# SH3_-_RS-485.net
KiCad netlist of a schematic drawn in Altium Designer
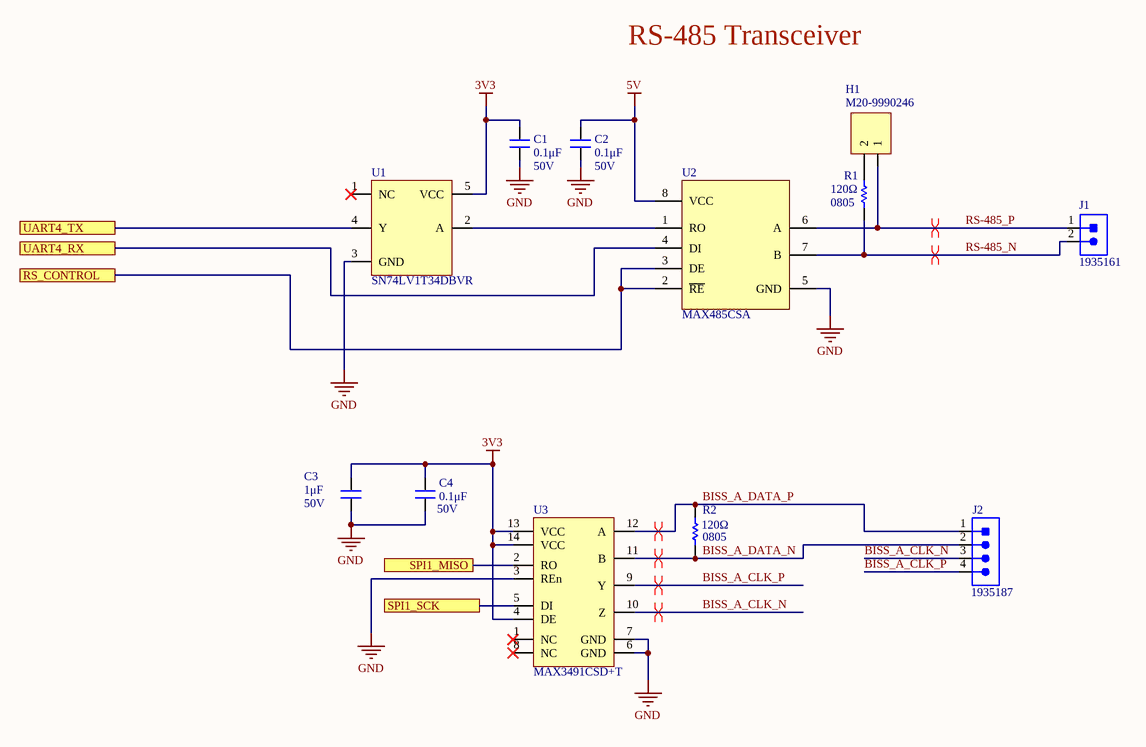
[diagram p0: SH3 - RS-485.SchDoc]

(export (version "E")
  (design (tool "Eeschema 10.0.6"))
  (components
    (comp (ref "C1")
      (value "0.1μF")
      (footprint "CAP2012")
      (description "CAP CER 0.1UF 50V X7R 0805")
      (fields
        (field (name "VOLTAGE RATING") "50V")
        (field (name "LCSC PART #") "C49678")
        (field (name "Comment") "CAP_0.1uF_50V_0805")
      )
      (libsource (lib "UWRT_Schematic_Library_2020") (part "CAP_0.1uF_50V_0805"))
    )
    (comp (ref "C2")
      (value "0.1μF")
      (footprint "CAP2012")
      (description "CAP CER 0.1UF 50V X7R 0805")
      (fields
        (field (name "VOLTAGE RATING") "50V")
        (field (name "LCSC PART #") "C49678")
        (field (name "Comment") "CAP_0.1uF_50V_0805")
      )
      (libsource (lib "UWRT_Schematic_Library_2020") (part "CAP_0.1uF_50V_0805"))
    )
    (comp (ref "C3")
      (value "1μF")
      (footprint "CAP2012")
      (description "CAP CER 1UF 50V X7R 0805")
      (fields
        (field (name "VOLTAGE RATING") "50V")
        (field (name "LCSC PART #") "C28323")
        (field (name "Comment") "CAP_1uF_50V_0805")
      )
      (libsource (lib "UWRT_Schematic_Library_2020") (part "CAP_1uF_50V_0805"))
    )
    (comp (ref "C4")
      (value "0.1μF")
      (footprint "CAP2012")
      (description "CAP CER 0.1UF 50V X7R 0805")
      (fields
        (field (name "VOLTAGE RATING") "50V")
        (field (name "LCSC PART #") "C49678")
        (field (name "Comment") "CAP_0.1uF_50V_0805")
      )
      (libsource (lib "UWRT_Schematic_Library_2020") (part "CAP_0.1uF_50V_0805"))
    )
    (comp (ref "H1")
      (value "JUMPER")
      (footprint "HDR1X2")
      (description "HEADER 2X1")
      (fields (field (name "MANUFACTURER PART NUMBER 1") "M20-9990246"))
      (libsource (lib "UWRT_Schematic_Library_2020") (part "JUMPER"))
    )
    (comp (ref "J1")
      (value "CON_2POS_SCREW_TERM")
      (footprint "1935161")
      (description "TERM BLK 2POS SIDE ENTRY 5MM")
      (fields (field (name "MANUFACTURER PART NUMBER 1") "1935161"))
      (libsource (lib "UWRT_Schematic_Library_2020") (part "CON_2POS_SCREW_TERM"))
    )
    (comp (ref "J2")
      (value "CON_4POS_SCREW_TERM")
      (footprint "1935187")
      (description "TERM BLK 4POS SIDE ENTRY 5MM")
      (fields (field (name "MANUFACTURER PART NUMBER 1") "1935187"))
      (libsource (lib "UWRT_Schematic_Library_2020") (part "CON_4POS_SCREW_TERM"))
    )
    (comp (ref "R1")
      (value "120Ω")
      (footprint "RESC0805")
      (description "RES 120 OHM 1% 1/8W 0805")
      (fields
        (field (name "LCSC PART #") "C17437")
        (field (name "PACKAGE/FOOTPRINT") "0805")
        (field (name "Comment") "RES_120Ω_0805_1%")
      )
      (libsource (lib "UWRT_Schematic_Library_2020") (part "RES_120Ω_0805_1%"))
    )
    (comp (ref "R2")
      (value "120Ω")
      (footprint "RESC0805")
      (description "RES 120 OHM 1% 1/8W 0805")
      (fields
        (field (name "PACKAGE/FOOTPRINT") "0805")
        (field (name "LCSC PART #") "C17437")
        (field (name "Comment") "RES_120Ω_0805_1%")
      )
      (libsource (lib "UWRT_Schematic_Library_2020") (part "RES_120Ω_0805_1%"))
    )
    (comp (ref "U1")
      (value "IC_BUFFER")
      (footprint "SN74LV1T34DBVR")
      (description "IC BUF NON-INVERT 5.5V SOT23-5")
      (fields
        (field (name "MANUFACTURER PART NUMBER 1") "SN74LV1T34DBVR")
        (field (name "LCSC PART #") "C100024")
      )
      (libsource (lib "UWRT_Schematic_Library_2020") (part "IC_BUFFER"))
    )
    (comp (ref "U2")
      (value "MAX485CSA")
      (footprint "SOIC127P600X175-8N")
      (description "IC RS485 TRANSCEIVER HALF 1/1 8SOIC")
      (fields (field (name "LCSC PART #") "C9945"))
      (libsource (lib "UWRT_Schematic_Library_2020") (part "MAX485CSA"))
    )
    (comp (ref "U3")
      (value "MAX3491")
      (footprint "MAX3491CSD+T")
      (description "IC RS485 TRANSCEIVER FULL 1/1 14SOIC")
      (fields (field (name "MANUFACTURER PART NUMBER 1") "MAX3491CSD+T"))
      (libsource (lib "UWRT_Schematic_Library_2020") (part "MAX3491"))
    )
  )
  (nets
    (net (code "1") (name "/BISS_A_CLK_N") (class "Default")
      (node (ref "J2") (pin "3") (pinfunction "3_3") (pintype "passive"))
      (node (ref "U3") (pin "10") (pinfunction "Z_10") (pintype "passive"))
    )
    (net (code "2") (name "/BISS_A_CLK_P") (class "Default")
      (node (ref "J2") (pin "4") (pinfunction "4_4") (pintype "passive"))
      (node (ref "U3") (pin "9") (pinfunction "Y_9") (pintype "passive"))
    )
    (net (code "3") (name "/BISS_A_DATA_N") (class "Default")
      (node (ref "J2") (pin "2") (pinfunction "2_2") (pintype "passive"))
      (node (ref "R2") (pin "1") (pinfunction "1_1") (pintype "passive"))
      (node (ref "U3") (pin "11") (pinfunction "B_11") (pintype "passive"))
    )
    (net (code "4") (name "/BISS_A_DATA_P") (class "Default")
      (node (ref "J2") (pin "1") (pinfunction "1_1") (pintype "passive"))
      (node (ref "R2") (pin "2") (pinfunction "2_2") (pintype "passive"))
      (node (ref "U3") (pin "12") (pinfunction "A_12") (pintype "passive"))
    )
    (net (code "5") (name "/RS-485_N") (class "Default")
      (node (ref "J1") (pin "2") (pinfunction "2_2") (pintype "passive"))
      (node (ref "R1") (pin "1") (pinfunction "1_1") (pintype "passive"))
      (node (ref "U2") (pin "7") (pinfunction "B_7") (pintype "passive"))
    )
    (net (code "6") (name "/RS-485_P") (class "Default")
      (node (ref "H1") (pin "1") (pinfunction "1_1") (pintype "passive"))
      (node (ref "J1") (pin "1") (pinfunction "1_1") (pintype "passive"))
      (node (ref "U2") (pin "6") (pinfunction "A_6") (pintype "passive"))
    )
    (net (code "7") (name "/RS_CONTROL") (class "Default")
      (node (ref "U2") (pin "2") (pinfunction "~{RE}_2") (pintype "passive"))
      (node (ref "U2") (pin "3") (pinfunction "DE_3") (pintype "passive"))
    )
    (net (code "8") (name "/SPI1_MISO") (class "Default")
      (node (ref "U3") (pin "2") (pinfunction "RO_2") (pintype "passive"))
    )
    (net (code "9") (name "/SPI1_SCK") (class "Default")
      (node (ref "U3") (pin "5") (pinfunction "DI_5") (pintype "passive"))
    )
    (net (code "10") (name "/UART4_RX") (class "Default")
      (node (ref "U2") (pin "4") (pinfunction "DI_4") (pintype "passive"))
    )
    (net (code "11") (name "/UART4_TX") (class "Default")
      (node (ref "U1") (pin "4") (pinfunction "Y_4") (pintype "passive"))
    )
    (net (code "12") (name "3V3") (class "Default")
      (node (ref "C1") (pin "1") (pinfunction "1_1") (pintype "passive"))
      (node (ref "C3") (pin "2") (pinfunction "2_2") (pintype "passive"))
      (node (ref "C4") (pin "2") (pinfunction "2_2") (pintype "passive"))
      (node (ref "U1") (pin "5") (pinfunction "VCC_5") (pintype "passive"))
      (node (ref "U3") (pin "13") (pinfunction "VCC_13") (pintype "passive"))
      (node (ref "U3") (pin "14") (pinfunction "VCC_14") (pintype "passive"))
      (node (ref "U3") (pin "4") (pinfunction "DE_4") (pintype "passive"))
    )
    (net (code "13") (name "5V") (class "Default")
      (node (ref "C2") (pin "1") (pinfunction "1_1") (pintype "passive"))
      (node (ref "U2") (pin "8") (pinfunction "VCC_8") (pintype "power_in"))
    )
    (net (code "14") (name "GND") (class "Default")
      (node (ref "C1") (pin "2") (pinfunction "2_2") (pintype "passive"))
      (node (ref "C2") (pin "2") (pinfunction "2_2") (pintype "passive"))
      (node (ref "C3") (pin "1") (pinfunction "1_1") (pintype "passive"))
      (node (ref "C4") (pin "1") (pinfunction "1_1") (pintype "passive"))
      (node (ref "U1") (pin "3") (pinfunction "GND_3") (pintype "passive"))
      (node (ref "U2") (pin "5") (pinfunction "GND_5") (pintype "power_in"))
      (node (ref "U3") (pin "3") (pinfunction "REn_3") (pintype "passive"))
      (node (ref "U3") (pin "6") (pinfunction "GND_6") (pintype "passive"))
      (node (ref "U3") (pin "7") (pinfunction "GND_7") (pintype "passive"))
    )
    (net (code "15") (name "Net-(H1-Pad2)") (class "Default")
      (node (ref "H1") (pin "2") (pinfunction "2_2") (pintype "passive"))
      (node (ref "R1") (pin "2") (pinfunction "2_2") (pintype "passive"))
    )
    (net (code "16") (name "Net-(U1-A)") (class "Default")
      (node (ref "U1") (pin "2") (pinfunction "A_2") (pintype "passive"))
      (node (ref "U2") (pin "1") (pinfunction "RO_1") (pintype "passive"))
    )
    (net (code "17") (name "unconnected-(U1-NC-Pad1)") (class "Default")
      (node (ref "U1") (pin "1") (pinfunction "NC_1") (pintype "passive+no_connect"))
    )
    (net (code "18") (name "unconnected-(U3-NC-Pad1)") (class "Default")
      (node (ref "U3") (pin "1") (pinfunction "NC_1") (pintype "passive+no_connect"))
    )
    (net (code "19") (name "unconnected-(U3-NC-Pad8)") (class "Default")
      (node (ref "U3") (pin "8") (pinfunction "NC_8") (pintype "passive+no_connect"))
    )
  )
)
